# supersaw.net
KiCad netlist of a schematic drawn in EAGLE
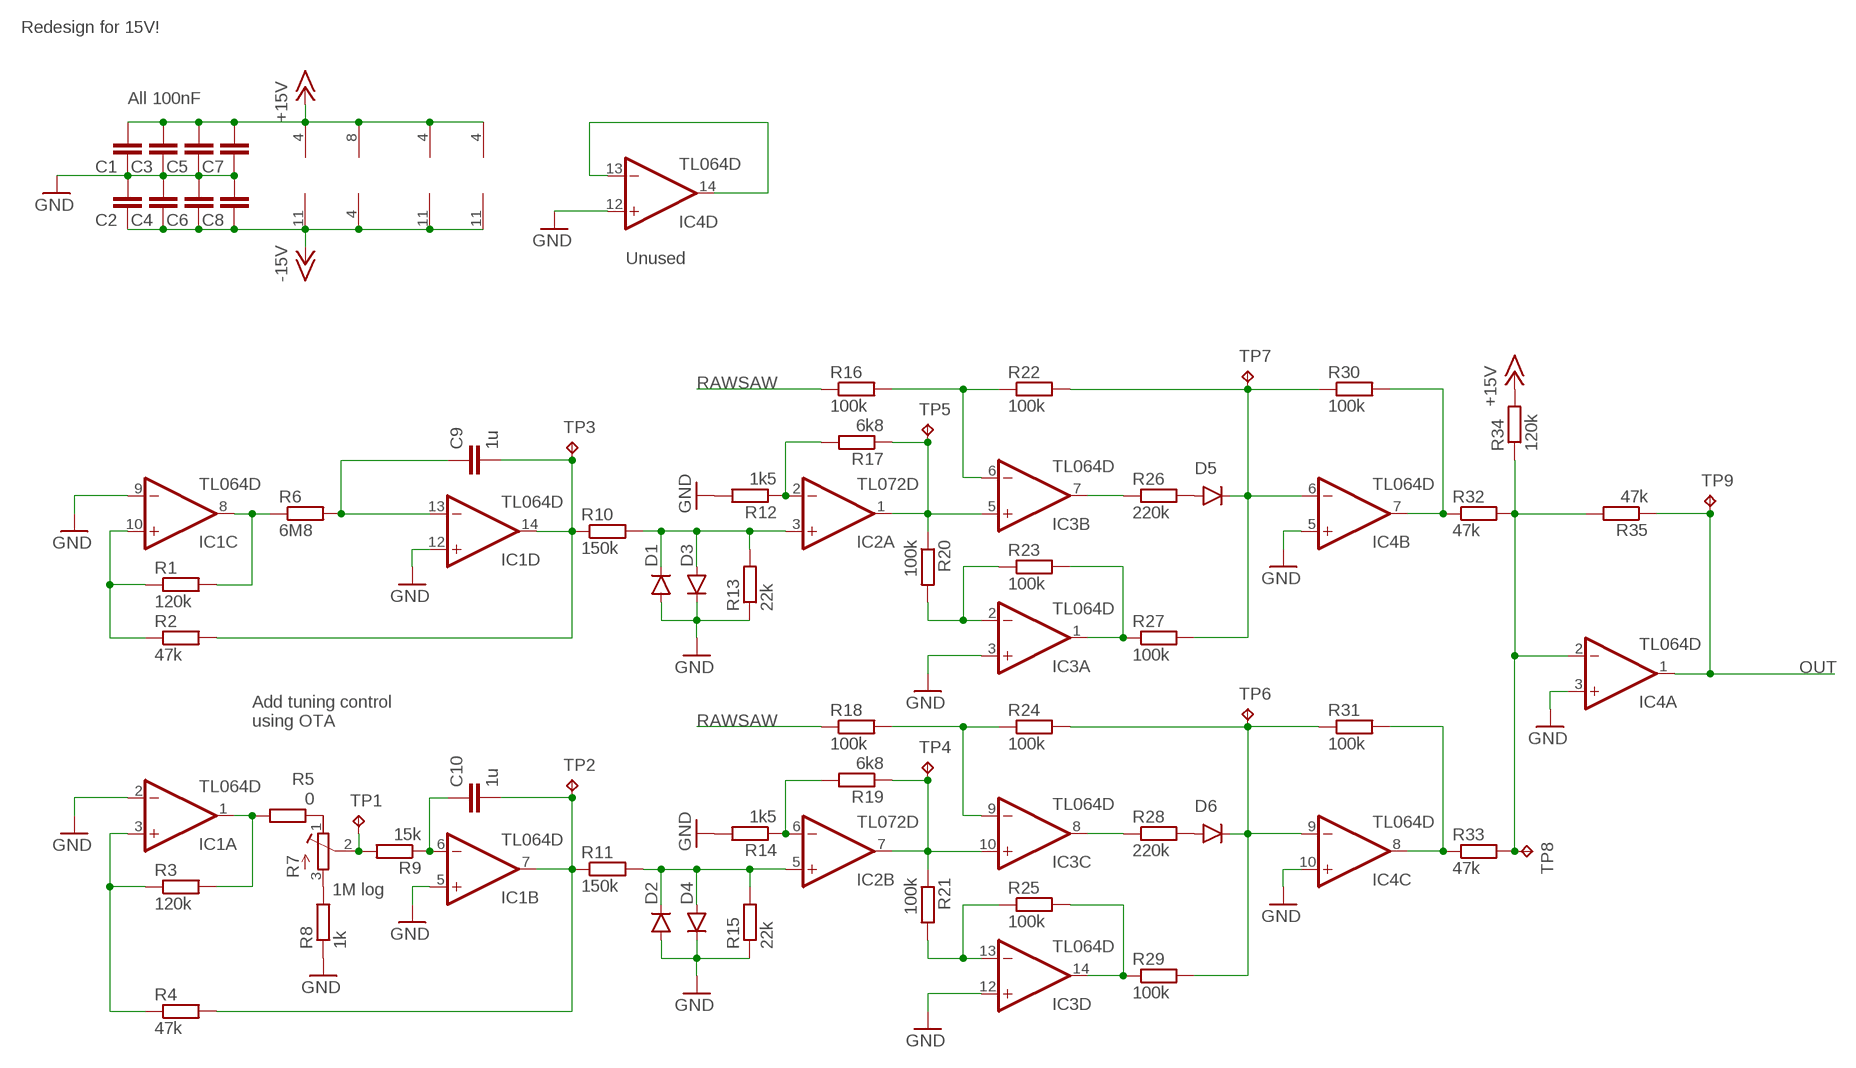
[diagram p0: schematic, sheet 1]

(export (version "E")
  (design (tool "Eeschema 10.0.6"))
  (components
    (comp (ref "C1")
      (value "100n")
      (footprint "eagle-import:C0805")
      (libsource (lib "eagle-import") (part "C-EUC0805"))
    )
    (comp (ref "C2")
      (value "100n")
      (footprint "eagle-import:C0805")
      (libsource (lib "eagle-import") (part "C-EUC0805"))
    )
    (comp (ref "C3")
      (value "100n")
      (footprint "eagle-import:C0805")
      (libsource (lib "eagle-import") (part "C-EUC0805"))
    )
    (comp (ref "C4")
      (value "100n")
      (footprint "eagle-import:C0805")
      (libsource (lib "eagle-import") (part "C-EUC0805"))
    )
    (comp (ref "C5")
      (value "100n")
      (footprint "eagle-import:C0805")
      (libsource (lib "eagle-import") (part "C-EUC0805"))
    )
    (comp (ref "C6")
      (value "100n")
      (footprint "eagle-import:C0805")
      (libsource (lib "eagle-import") (part "C-EUC0805"))
    )
    (comp (ref "C7")
      (value "100n")
      (footprint "eagle-import:C0805")
      (libsource (lib "eagle-import") (part "C-EUC0805"))
    )
    (comp (ref "C8")
      (value "100n")
      (footprint "eagle-import:C0805")
      (libsource (lib "eagle-import") (part "C-EUC0805"))
    )
    (comp (ref "C9")
      (value "1u")
      (footprint "eagle-import:C0805")
      (libsource (lib "eagle-import") (part "C-EUC0805"))
    )
    (comp (ref "C10")
      (value "1u")
      (footprint "eagle-import:C0805")
      (libsource (lib "eagle-import") (part "C-EUC0805"))
    )
    (comp (ref "D1")
      (value "1N41480805")
      (footprint "eagle-import:D0805-J")
      (libsource (lib "eagle-import") (part "1N41480805"))
    )
    (comp (ref "D2")
      (value "1N41480805")
      (footprint "eagle-import:D0805-J")
      (libsource (lib "eagle-import") (part "1N41480805"))
    )
    (comp (ref "D3")
      (value "1N41480805")
      (footprint "eagle-import:D0805-J")
      (libsource (lib "eagle-import") (part "1N41480805"))
    )
    (comp (ref "D4")
      (value "1N41480805")
      (footprint "eagle-import:D0805-J")
      (libsource (lib "eagle-import") (part "1N41480805"))
    )
    (comp (ref "D5")
      (value "1N41480805")
      (footprint "eagle-import:D0805-J")
      (libsource (lib "eagle-import") (part "1N41480805"))
    )
    (comp (ref "D6")
      (value "1N41480805")
      (footprint "eagle-import:D0805-J")
      (libsource (lib "eagle-import") (part "1N41480805"))
    )
    (comp (ref "IC1")
      (value "TL064D")
      (footprint "eagle-import:SO14")
      (libsource (lib "eagle-import") (part "TL064D"))
    )
    (comp (ref "IC2")
      (value "TL072D")
      (footprint "eagle-import:SO08J")
      (libsource (lib "eagle-import") (part "TL072D"))
    )
    (comp (ref "IC3")
      (value "TL064D")
      (footprint "eagle-import:SO14")
      (libsource (lib "eagle-import") (part "TL064D"))
    )
    (comp (ref "IC4")
      (value "TL064D")
      (footprint "eagle-import:SO14")
      (libsource (lib "eagle-import") (part "TL064D"))
    )
    (comp (ref "R1")
      (value "120k")
      (footprint "eagle-import:R0805")
      (libsource (lib "eagle-import") (part "R-EU_R0805"))
    )
    (comp (ref "R2")
      (value "47k")
      (footprint "eagle-import:R0805")
      (libsource (lib "eagle-import") (part "R-EU_R0805"))
    )
    (comp (ref "R3")
      (value "120k")
      (footprint "eagle-import:R0805")
      (libsource (lib "eagle-import") (part "R-EU_R0805"))
    )
    (comp (ref "R4")
      (value "47k")
      (footprint "eagle-import:R0805")
      (libsource (lib "eagle-import") (part "R-EU_R0805"))
    )
    (comp (ref "R5")
      (value "0")
      (footprint "eagle-import:R0805")
      (libsource (lib "eagle-import") (part "R-EU_R0805"))
    )
    (comp (ref "R6")
      (value "6M8")
      (footprint "eagle-import:R0805")
      (libsource (lib "eagle-import") (part "R-EU_R0805"))
    )
    (comp (ref "R7")
      (value "1M log")
      (footprint "eagle-import:RTRIMT93XA")
      (libsource (lib "eagle-import") (part "R-TRIMMT93XA"))
    )
    (comp (ref "R8")
      (value "1k")
      (footprint "eagle-import:R0805")
      (libsource (lib "eagle-import") (part "R-EU_R0805"))
    )
    (comp (ref "R9")
      (value "15k")
      (footprint "eagle-import:R0805")
      (libsource (lib "eagle-import") (part "R-EU_R0805"))
    )
    (comp (ref "R10")
      (value "150k")
      (footprint "eagle-import:R0805")
      (libsource (lib "eagle-import") (part "R-EU_R0805"))
    )
    (comp (ref "R11")
      (value "150k")
      (footprint "eagle-import:R0805")
      (libsource (lib "eagle-import") (part "R-EU_R0805"))
    )
    (comp (ref "R12")
      (value "1k5")
      (footprint "eagle-import:R0805")
      (libsource (lib "eagle-import") (part "R-EU_R0805"))
    )
    (comp (ref "R13")
      (value "22k")
      (footprint "eagle-import:R0805")
      (libsource (lib "eagle-import") (part "R-EU_R0805"))
    )
    (comp (ref "R14")
      (value "1k5")
      (footprint "eagle-import:R0805")
      (libsource (lib "eagle-import") (part "R-EU_R0805"))
    )
    (comp (ref "R15")
      (value "22k")
      (footprint "eagle-import:R0805")
      (libsource (lib "eagle-import") (part "R-EU_R0805"))
    )
    (comp (ref "R16")
      (value "100k")
      (footprint "eagle-import:R0805")
      (libsource (lib "eagle-import") (part "R-EU_R0805"))
    )
    (comp (ref "R17")
      (value "6k8")
      (footprint "eagle-import:R0805")
      (libsource (lib "eagle-import") (part "R-EU_R0805"))
    )
    (comp (ref "R18")
      (value "100k")
      (footprint "eagle-import:R0805")
      (libsource (lib "eagle-import") (part "R-EU_R0805"))
    )
    (comp (ref "R19")
      (value "6k8")
      (footprint "eagle-import:R0805")
      (libsource (lib "eagle-import") (part "R-EU_R0805"))
    )
    (comp (ref "R20")
      (value "100k")
      (footprint "eagle-import:R0805")
      (libsource (lib "eagle-import") (part "R-EU_R0805"))
    )
    (comp (ref "R21")
      (value "100k")
      (footprint "eagle-import:R0805")
      (libsource (lib "eagle-import") (part "R-EU_R0805"))
    )
    (comp (ref "R22")
      (value "100k")
      (footprint "eagle-import:R0805")
      (libsource (lib "eagle-import") (part "R-EU_R0805"))
    )
    (comp (ref "R23")
      (value "100k")
      (footprint "eagle-import:R0805")
      (libsource (lib "eagle-import") (part "R-EU_R0805"))
    )
    (comp (ref "R24")
      (value "100k")
      (footprint "eagle-import:R0805")
      (libsource (lib "eagle-import") (part "R-EU_R0805"))
    )
    (comp (ref "R25")
      (value "100k")
      (footprint "eagle-import:R0805")
      (libsource (lib "eagle-import") (part "R-EU_R0805"))
    )
    (comp (ref "R26")
      (value "220k")
      (footprint "eagle-import:R0805")
      (libsource (lib "eagle-import") (part "R-EU_R0805"))
    )
    (comp (ref "R27")
      (value "100k")
      (footprint "eagle-import:R0805")
      (libsource (lib "eagle-import") (part "R-EU_R0805"))
    )
    (comp (ref "R28")
      (value "220k")
      (footprint "eagle-import:R0805")
      (libsource (lib "eagle-import") (part "R-EU_R0805"))
    )
    (comp (ref "R29")
      (value "100k")
      (footprint "eagle-import:R0805")
      (libsource (lib "eagle-import") (part "R-EU_R0805"))
    )
    (comp (ref "R30")
      (value "100k")
      (footprint "eagle-import:R0805")
      (libsource (lib "eagle-import") (part "R-EU_R0805"))
    )
    (comp (ref "R31")
      (value "100k")
      (footprint "eagle-import:R0805")
      (libsource (lib "eagle-import") (part "R-EU_R0805"))
    )
    (comp (ref "R32")
      (value "47k")
      (footprint "eagle-import:R0805")
      (libsource (lib "eagle-import") (part "R-EU_R0805"))
    )
    (comp (ref "R33")
      (value "47k")
      (footprint "eagle-import:R0805")
      (libsource (lib "eagle-import") (part "R-EU_R0805"))
    )
    (comp (ref "R34")
      (value "120k")
      (footprint "eagle-import:R0805")
      (libsource (lib "eagle-import") (part "R-EU_R0805"))
    )
    (comp (ref "R35")
      (value "47k")
      (footprint "eagle-import:R0805")
      (libsource (lib "eagle-import") (part "R-EU_R0805"))
    )
    (comp (ref "TP1")
      (value "TPB2,54")
      (footprint "eagle-import:B2,54")
      (libsource (lib "eagle-import") (part "TPB2,54"))
    )
    (comp (ref "TP2")
      (value "TPB2,54")
      (footprint "eagle-import:B2,54")
      (libsource (lib "eagle-import") (part "TPB2,54"))
    )
    (comp (ref "TP3")
      (value "TPB2,54")
      (footprint "eagle-import:B2,54")
      (libsource (lib "eagle-import") (part "TPB2,54"))
    )
    (comp (ref "TP4")
      (value "TPB2,54")
      (footprint "eagle-import:B2,54")
      (libsource (lib "eagle-import") (part "TPB2,54"))
    )
    (comp (ref "TP5")
      (value "TPB2,54")
      (footprint "eagle-import:B2,54")
      (libsource (lib "eagle-import") (part "TPB2,54"))
    )
    (comp (ref "TP6")
      (value "TPB2,54")
      (footprint "eagle-import:B2,54")
      (libsource (lib "eagle-import") (part "TPB2,54"))
    )
    (comp (ref "TP7")
      (value "TPB2,54")
      (footprint "eagle-import:B2,54")
      (libsource (lib "eagle-import") (part "TPB2,54"))
    )
    (comp (ref "TP8")
      (value "TPB2,54")
      (footprint "eagle-import:B2,54")
      (libsource (lib "eagle-import") (part "TPB2,54"))
    )
    (comp (ref "TP9")
      (value "TPB2,54")
      (footprint "eagle-import:B2,54")
      (libsource (lib "eagle-import") (part "TPB2,54"))
    )
  )
  (nets
    (net (code "1") (name "+15V") (class "Default")
      (node (ref "C1") (pin "2") (pinfunction "2_2") (pintype "passive"))
      (node (ref "C3") (pin "2") (pinfunction "2_2") (pintype "passive"))
      (node (ref "C5") (pin "2") (pinfunction "2_2") (pintype "passive"))
      (node (ref "C7") (pin "2") (pinfunction "2_2") (pintype "passive"))
      (node (ref "IC1") (pin "4") (pinfunction "V+_4") (pintype "power_in"))
      (node (ref "IC2") (pin "8") (pinfunction "V+_8") (pintype "power_in"))
      (node (ref "IC3") (pin "4") (pinfunction "V+_4") (pintype "power_in"))
      (node (ref "IC4") (pin "4") (pinfunction "V+_4") (pintype "power_in"))
      (node (ref "R34") (pin "2") (pinfunction "2_2") (pintype "passive"))
    )
    (net (code "2") (name "-15V") (class "Default")
      (node (ref "C2") (pin "1") (pinfunction "1_1") (pintype "passive"))
      (node (ref "C4") (pin "1") (pinfunction "1_1") (pintype "passive"))
      (node (ref "C6") (pin "1") (pinfunction "1_1") (pintype "passive"))
      (node (ref "C8") (pin "1") (pinfunction "1_1") (pintype "passive"))
      (node (ref "IC1") (pin "11") (pinfunction "V-_11") (pintype "power_in"))
      (node (ref "IC2") (pin "4") (pinfunction "V-_4") (pintype "power_in"))
      (node (ref "IC3") (pin "11") (pinfunction "V-_11") (pintype "power_in"))
      (node (ref "IC4") (pin "11") (pinfunction "V-_11") (pintype "power_in"))
    )
    (net (code "3") (name "GND") (class "Default")
      (node (ref "C1") (pin "1") (pinfunction "1_1") (pintype "passive"))
      (node (ref "C2") (pin "2") (pinfunction "2_2") (pintype "passive"))
      (node (ref "C3") (pin "1") (pinfunction "1_1") (pintype "passive"))
      (node (ref "C4") (pin "2") (pinfunction "2_2") (pintype "passive"))
      (node (ref "C5") (pin "1") (pinfunction "1_1") (pintype "passive"))
      (node (ref "C6") (pin "2") (pinfunction "2_2") (pintype "passive"))
      (node (ref "C7") (pin "1") (pinfunction "1_1") (pintype "passive"))
      (node (ref "C8") (pin "2") (pinfunction "2_2") (pintype "passive"))
      (node (ref "D1") (pin "A") (pinfunction "A_A") (pintype "passive"))
      (node (ref "D2") (pin "A") (pinfunction "A_A") (pintype "passive"))
      (node (ref "D3") (pin "C") (pinfunction "C_C") (pintype "passive"))
      (node (ref "D4") (pin "C") (pinfunction "C_C") (pintype "passive"))
      (node (ref "IC1") (pin "12") (pinfunction "+IN_12") (pintype "input"))
      (node (ref "IC1") (pin "2") (pinfunction "-IN_2") (pintype "input"))
      (node (ref "IC1") (pin "5") (pinfunction "+IN_5") (pintype "input"))
      (node (ref "IC1") (pin "9") (pinfunction "-IN_9") (pintype "input"))
      (node (ref "IC3") (pin "12") (pinfunction "+IN_12") (pintype "input"))
      (node (ref "IC3") (pin "3") (pinfunction "+IN_3") (pintype "input"))
      (node (ref "IC4") (pin "10") (pinfunction "+IN_10") (pintype "input"))
      (node (ref "IC4") (pin "12") (pinfunction "+IN_12") (pintype "input"))
      (node (ref "IC4") (pin "3") (pinfunction "+IN_3") (pintype "input"))
      (node (ref "IC4") (pin "5") (pinfunction "+IN_5") (pintype "input"))
      (node (ref "R12") (pin "2") (pinfunction "2_2") (pintype "passive"))
      (node (ref "R13") (pin "1") (pinfunction "1_1") (pintype "passive"))
      (node (ref "R14") (pin "2") (pinfunction "2_2") (pintype "passive"))
      (node (ref "R15") (pin "1") (pinfunction "1_1") (pintype "passive"))
      (node (ref "R8") (pin "1") (pinfunction "1_1") (pintype "passive"))
    )
    (net (code "4") (name "Net-(D5-PadA)") (class "Default")
      (node (ref "D5") (pin "A") (pinfunction "A_A") (pintype "passive"))
      (node (ref "R26") (pin "2") (pinfunction "2_2") (pintype "passive"))
    )
    (net (code "5") (name "Net-(D6-PadA)") (class "Default")
      (node (ref "D6") (pin "A") (pinfunction "A_A") (pintype "passive"))
      (node (ref "R28") (pin "2") (pinfunction "2_2") (pintype "passive"))
    )
    (net (code "6") (name "Net-(IC1A-+IN)") (class "Default")
      (node (ref "IC1") (pin "3") (pinfunction "+IN_3") (pintype "input"))
      (node (ref "R3") (pin "1") (pinfunction "1_1") (pintype "passive"))
      (node (ref "R4") (pin "1") (pinfunction "1_1") (pintype "passive"))
    )
    (net (code "7") (name "Net-(IC1A-OUT)") (class "Default")
      (node (ref "IC1") (pin "1") (pinfunction "OUT_1") (pintype "output"))
      (node (ref "R3") (pin "2") (pinfunction "2_2") (pintype "passive"))
      (node (ref "R5") (pin "2") (pinfunction "2_2") (pintype "passive"))
    )
    (net (code "8") (name "Net-(IC1B--IN)") (class "Default")
      (node (ref "C10") (pin "1") (pinfunction "1_1") (pintype "passive"))
      (node (ref "IC1") (pin "6") (pinfunction "-IN_6") (pintype "input"))
      (node (ref "R9") (pin "1") (pinfunction "1_1") (pintype "passive"))
    )
    (net (code "9") (name "Net-(IC1B-OUT)") (class "Default")
      (node (ref "C10") (pin "2") (pinfunction "2_2") (pintype "passive"))
      (node (ref "IC1") (pin "7") (pinfunction "OUT_7") (pintype "output"))
      (node (ref "R11") (pin "1") (pinfunction "1_1") (pintype "passive"))
      (node (ref "R4") (pin "2") (pinfunction "2_2") (pintype "passive"))
      (node (ref "TP2") (pin "TP") (pinfunction "TP_TP") (pintype "input"))
    )
    (net (code "10") (name "Net-(IC1C-+IN)") (class "Default")
      (node (ref "IC1") (pin "10") (pinfunction "+IN_10") (pintype "input"))
      (node (ref "R1") (pin "1") (pinfunction "1_1") (pintype "passive"))
      (node (ref "R2") (pin "1") (pinfunction "1_1") (pintype "passive"))
    )
    (net (code "11") (name "Net-(IC1C-OUT)") (class "Default")
      (node (ref "IC1") (pin "8") (pinfunction "OUT_8") (pintype "output"))
      (node (ref "R1") (pin "2") (pinfunction "2_2") (pintype "passive"))
      (node (ref "R6") (pin "1") (pinfunction "1_1") (pintype "passive"))
    )
    (net (code "12") (name "Net-(IC1D--IN)") (class "Default")
      (node (ref "C9") (pin "1") (pinfunction "1_1") (pintype "passive"))
      (node (ref "IC1") (pin "13") (pinfunction "-IN_13") (pintype "input"))
      (node (ref "R6") (pin "2") (pinfunction "2_2") (pintype "passive"))
    )
    (net (code "13") (name "Net-(IC1D-OUT)") (class "Default")
      (node (ref "C9") (pin "2") (pinfunction "2_2") (pintype "passive"))
      (node (ref "IC1") (pin "14") (pinfunction "OUT_14") (pintype "output"))
      (node (ref "R10") (pin "1") (pinfunction "1_1") (pintype "passive"))
      (node (ref "R2") (pin "2") (pinfunction "2_2") (pintype "passive"))
      (node (ref "TP3") (pin "TP") (pinfunction "TP_TP") (pintype "input"))
    )
    (net (code "14") (name "Net-(IC2A-+IN)") (class "Default")
      (node (ref "D1") (pin "C") (pinfunction "C_C") (pintype "passive"))
      (node (ref "D3") (pin "A") (pinfunction "A_A") (pintype "passive"))
      (node (ref "IC2") (pin "3") (pinfunction "+IN_3") (pintype "input"))
      (node (ref "R10") (pin "2") (pinfunction "2_2") (pintype "passive"))
      (node (ref "R13") (pin "2") (pinfunction "2_2") (pintype "passive"))
    )
    (net (code "15") (name "Net-(IC2A--IN)") (class "Default")
      (node (ref "IC2") (pin "2") (pinfunction "-IN_2") (pintype "input"))
      (node (ref "R12") (pin "1") (pinfunction "1_1") (pintype "passive"))
      (node (ref "R17") (pin "2") (pinfunction "2_2") (pintype "passive"))
    )
    (net (code "16") (name "Net-(IC2A-OUT)") (class "Default")
      (node (ref "IC2") (pin "1") (pinfunction "OUT_1") (pintype "output"))
      (node (ref "IC3") (pin "5") (pinfunction "+IN_5") (pintype "input"))
      (node (ref "R17") (pin "1") (pinfunction "1_1") (pintype "passive"))
      (node (ref "R20") (pin "1") (pinfunction "1_1") (pintype "passive"))
      (node (ref "TP5") (pin "TP") (pinfunction "TP_TP") (pintype "input"))
    )
    (net (code "17") (name "Net-(IC2B-+IN)") (class "Default")
      (node (ref "D2") (pin "C") (pinfunction "C_C") (pintype "passive"))
      (node (ref "D4") (pin "A") (pinfunction "A_A") (pintype "passive"))
      (node (ref "IC2") (pin "5") (pinfunction "+IN_5") (pintype "input"))
      (node (ref "R11") (pin "2") (pinfunction "2_2") (pintype "passive"))
      (node (ref "R15") (pin "2") (pinfunction "2_2") (pintype "passive"))
    )
    (net (code "18") (name "Net-(IC2B--IN)") (class "Default")
      (node (ref "IC2") (pin "6") (pinfunction "-IN_6") (pintype "input"))
      (node (ref "R14") (pin "1") (pinfunction "1_1") (pintype "passive"))
      (node (ref "R19") (pin "2") (pinfunction "2_2") (pintype "passive"))
    )
    (net (code "19") (name "Net-(IC2B-OUT)") (class "Default")
      (node (ref "IC2") (pin "7") (pinfunction "OUT_7") (pintype "output"))
      (node (ref "IC3") (pin "10") (pinfunction "+IN_10") (pintype "input"))
      (node (ref "R19") (pin "1") (pinfunction "1_1") (pintype "passive"))
      (node (ref "R21") (pin "1") (pinfunction "1_1") (pintype "passive"))
      (node (ref "TP4") (pin "TP") (pinfunction "TP_TP") (pintype "input"))
    )
    (net (code "20") (name "Net-(IC3A--IN)") (class "Default")
      (node (ref "IC3") (pin "2") (pinfunction "-IN_2") (pintype "input"))
      (node (ref "R20") (pin "2") (pinfunction "2_2") (pintype "passive"))
      (node (ref "R23") (pin "1") (pinfunction "1_1") (pintype "passive"))
    )
    (net (code "21") (name "Net-(IC3A-OUT)") (class "Default")
      (node (ref "IC3") (pin "1") (pinfunction "OUT_1") (pintype "output"))
      (node (ref "R23") (pin "2") (pinfunction "2_2") (pintype "passive"))
      (node (ref "R27") (pin "1") (pinfunction "1_1") (pintype "passive"))
    )
    (net (code "22") (name "Net-(IC3B--IN)") (class "Default")
      (node (ref "IC3") (pin "6") (pinfunction "-IN_6") (pintype "input"))
      (node (ref "R16") (pin "2") (pinfunction "2_2") (pintype "passive"))
      (node (ref "R22") (pin "1") (pinfunction "1_1") (pintype "passive"))
    )
    (net (code "23") (name "Net-(IC3B-OUT)") (class "Default")
      (node (ref "IC3") (pin "7") (pinfunction "OUT_7") (pintype "output"))
      (node (ref "R26") (pin "1") (pinfunction "1_1") (pintype "passive"))
    )
    (net (code "24") (name "Net-(IC3C--IN)") (class "Default")
      (node (ref "IC3") (pin "9") (pinfunction "-IN_9") (pintype "input"))
      (node (ref "R18") (pin "2") (pinfunction "2_2") (pintype "passive"))
      (node (ref "R24") (pin "1") (pinfunction "1_1") (pintype "passive"))
    )
    (net (code "25") (name "Net-(IC3C-OUT)") (class "Default")
      (node (ref "IC3") (pin "8") (pinfunction "OUT_8") (pintype "output"))
      (node (ref "R28") (pin "1") (pinfunction "1_1") (pintype "passive"))
    )
    (net (code "26") (name "Net-(IC3D--IN)") (class "Default")
      (node (ref "IC3") (pin "13") (pinfunction "-IN_13") (pintype "input"))
      (node (ref "R21") (pin "2") (pinfunction "2_2") (pintype "passive"))
      (node (ref "R25") (pin "1") (pinfunction "1_1") (pintype "passive"))
    )
    (net (code "27") (name "Net-(IC3D-OUT)") (class "Default")
      (node (ref "IC3") (pin "14") (pinfunction "OUT_14") (pintype "output"))
      (node (ref "R25") (pin "2") (pinfunction "2_2") (pintype "passive"))
      (node (ref "R29") (pin "1") (pinfunction "1_1") (pintype "passive"))
    )
    (net (code "28") (name "Net-(IC4A--IN)") (class "Default")
      (node (ref "IC4") (pin "2") (pinfunction "-IN_2") (pintype "input"))
      (node (ref "R32") (pin "2") (pinfunction "2_2") (pintype "passive"))
      (node (ref "R33") (pin "2") (pinfunction "2_2") (pintype "passive"))
      (node (ref "R34") (pin "1") (pinfunction "1_1") (pintype "passive"))
      (node (ref "R35") (pin "2") (pinfunction "2_2") (pintype "passive"))
      (node (ref "TP8") (pin "TP") (pinfunction "TP_TP") (pintype "input"))
    )
    (net (code "29") (name "Net-(IC4B--IN)") (class "Default")
      (node (ref "D5") (pin "C") (pinfunction "C_C") (pintype "passive"))
      (node (ref "IC4") (pin "6") (pinfunction "-IN_6") (pintype "input"))
      (node (ref "R22") (pin "2") (pinfunction "2_2") (pintype "passive"))
      (node (ref "R27") (pin "2") (pinfunction "2_2") (pintype "passive"))
      (node (ref "R30") (pin "1") (pinfunction "1_1") (pintype "passive"))
      (node (ref "TP7") (pin "TP") (pinfunction "TP_TP") (pintype "input"))
    )
    (net (code "30") (name "Net-(IC4B-OUT)") (class "Default")
      (node (ref "IC4") (pin "7") (pinfunction "OUT_7") (pintype "output"))
      (node (ref "R30") (pin "2") (pinfunction "2_2") (pintype "passive"))
      (node (ref "R32") (pin "1") (pinfunction "1_1") (pintype "passive"))
    )
    (net (code "31") (name "Net-(IC4C--IN)") (class "Default")
      (node (ref "D6") (pin "C") (pinfunction "C_C") (pintype "passive"))
      (node (ref "IC4") (pin "9") (pinfunction "-IN_9") (pintype "input"))
      (node (ref "R24") (pin "2") (pinfunction "2_2") (pintype "passive"))
      (node (ref "R29") (pin "2") (pinfunction "2_2") (pintype "passive"))
      (node (ref "R31") (pin "1") (pinfunction "1_1") (pintype "passive"))
      (node (ref "TP6") (pin "TP") (pinfunction "TP_TP") (pintype "input"))
    )
    (net (code "32") (name "Net-(IC4C-OUT)") (class "Default")
      (node (ref "IC4") (pin "8") (pinfunction "OUT_8") (pintype "output"))
      (node (ref "R31") (pin "2") (pinfunction "2_2") (pintype "passive"))
      (node (ref "R33") (pin "1") (pinfunction "1_1") (pintype "passive"))
    )
    (net (code "33") (name "Net-(IC4D--IN)") (class "Default")
      (node (ref "IC4") (pin "13") (pinfunction "-IN_13") (pintype "input"))
      (node (ref "IC4") (pin "14") (pinfunction "OUT_14") (pintype "output"))
    )
    (net (code "34") (name "Net-(R7-A)") (class "Default")
      (node (ref "R5") (pin "1") (pinfunction "1_1") (pintype "passive"))
      (node (ref "R7") (pin "1") (pinfunction "A_1") (pintype "passive"))
    )
    (net (code "35") (name "Net-(R7-E)") (class "Default")
      (node (ref "R7") (pin "3") (pinfunction "E_3") (pintype "passive"))
      (node (ref "R8") (pin "2") (pinfunction "2_2") (pintype "passive"))
    )
    (net (code "36") (name "Net-(R7-S)") (class "Default")
      (node (ref "R7") (pin "2") (pinfunction "S_2") (pintype "passive"))
      (node (ref "R9") (pin "2") (pinfunction "2_2") (pintype "passive"))
      (node (ref "TP1") (pin "TP") (pinfunction "TP_TP") (pintype "input"))
    )
    (net (code "37") (name "OUT") (class "Default")
      (node (ref "IC4") (pin "1") (pinfunction "OUT_1") (pintype "output"))
      (node (ref "R35") (pin "1") (pinfunction "1_1") (pintype "passive"))
      (node (ref "TP9") (pin "TP") (pinfunction "TP_TP") (pintype "input"))
    )
    (net (code "38") (name "RAWSAW") (class "Default")
      (node (ref "R16") (pin "1") (pinfunction "1_1") (pintype "passive"))
      (node (ref "R18") (pin "1") (pinfunction "1_1") (pintype "passive"))
    )
  )
)
